# SCH_555-Circuit_2025-10-18.net
KiCad netlist of a schematic drawn in EasyEDA
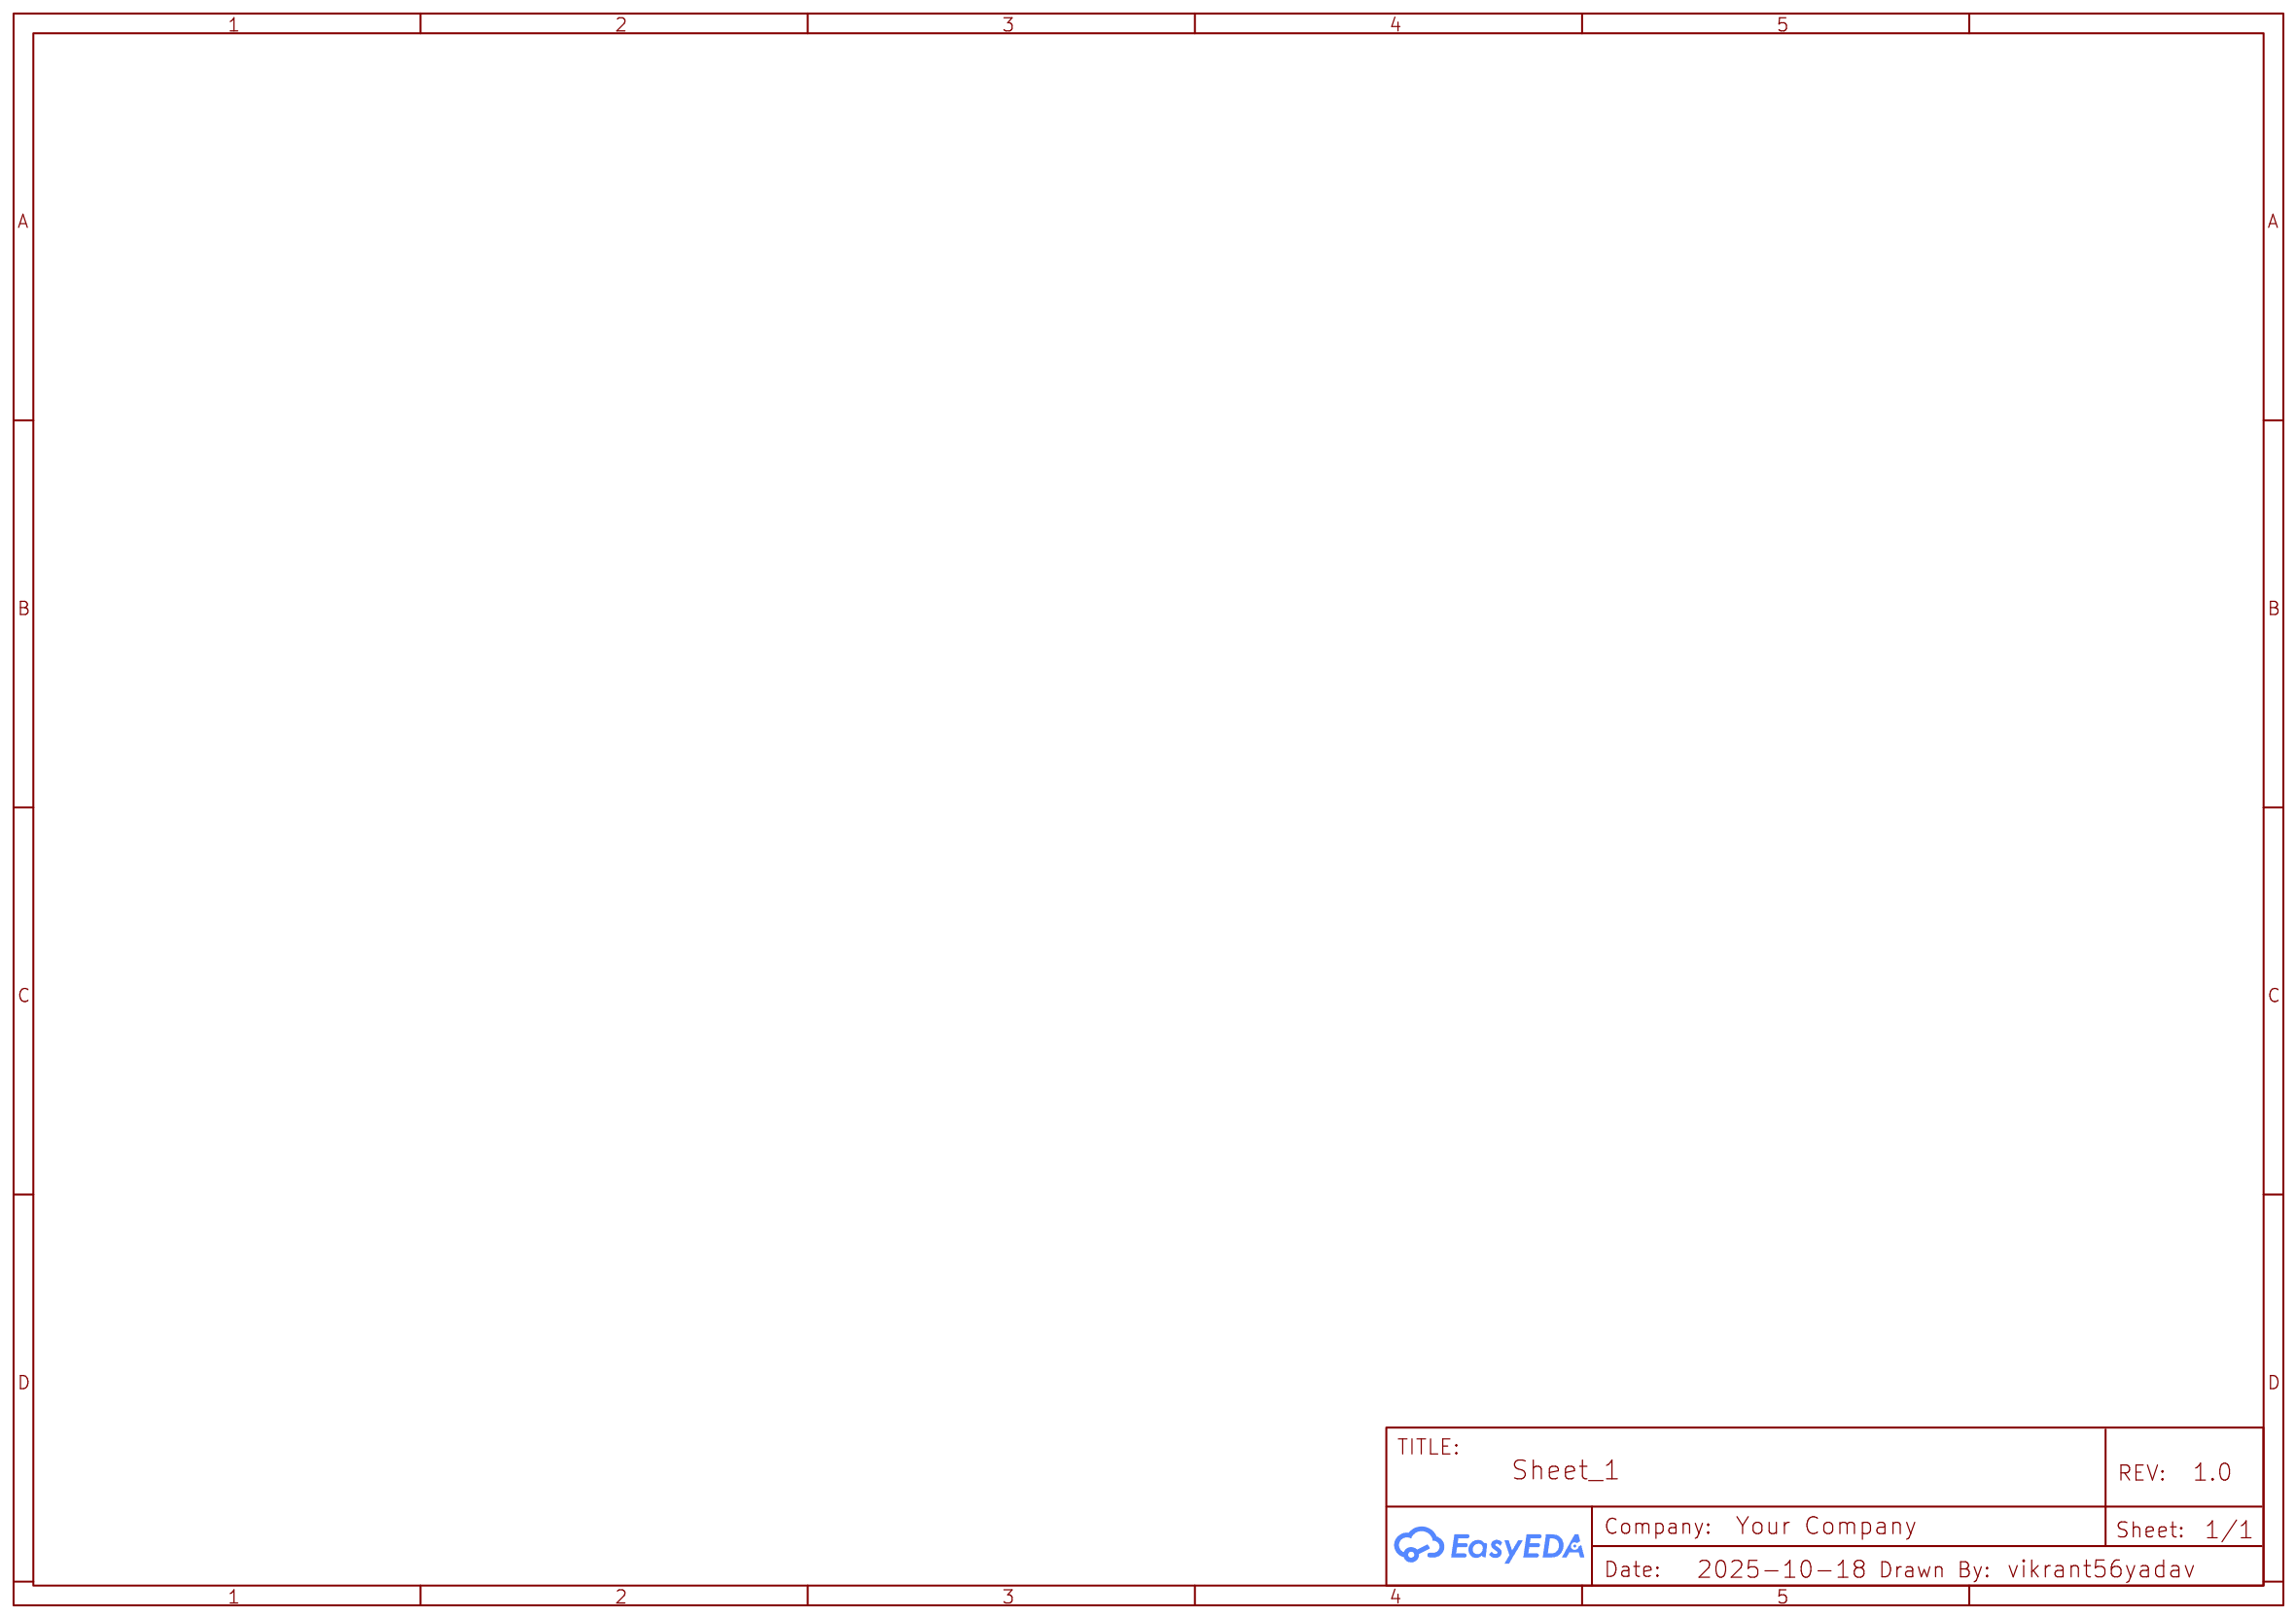
[diagram p0: Sheet_1]
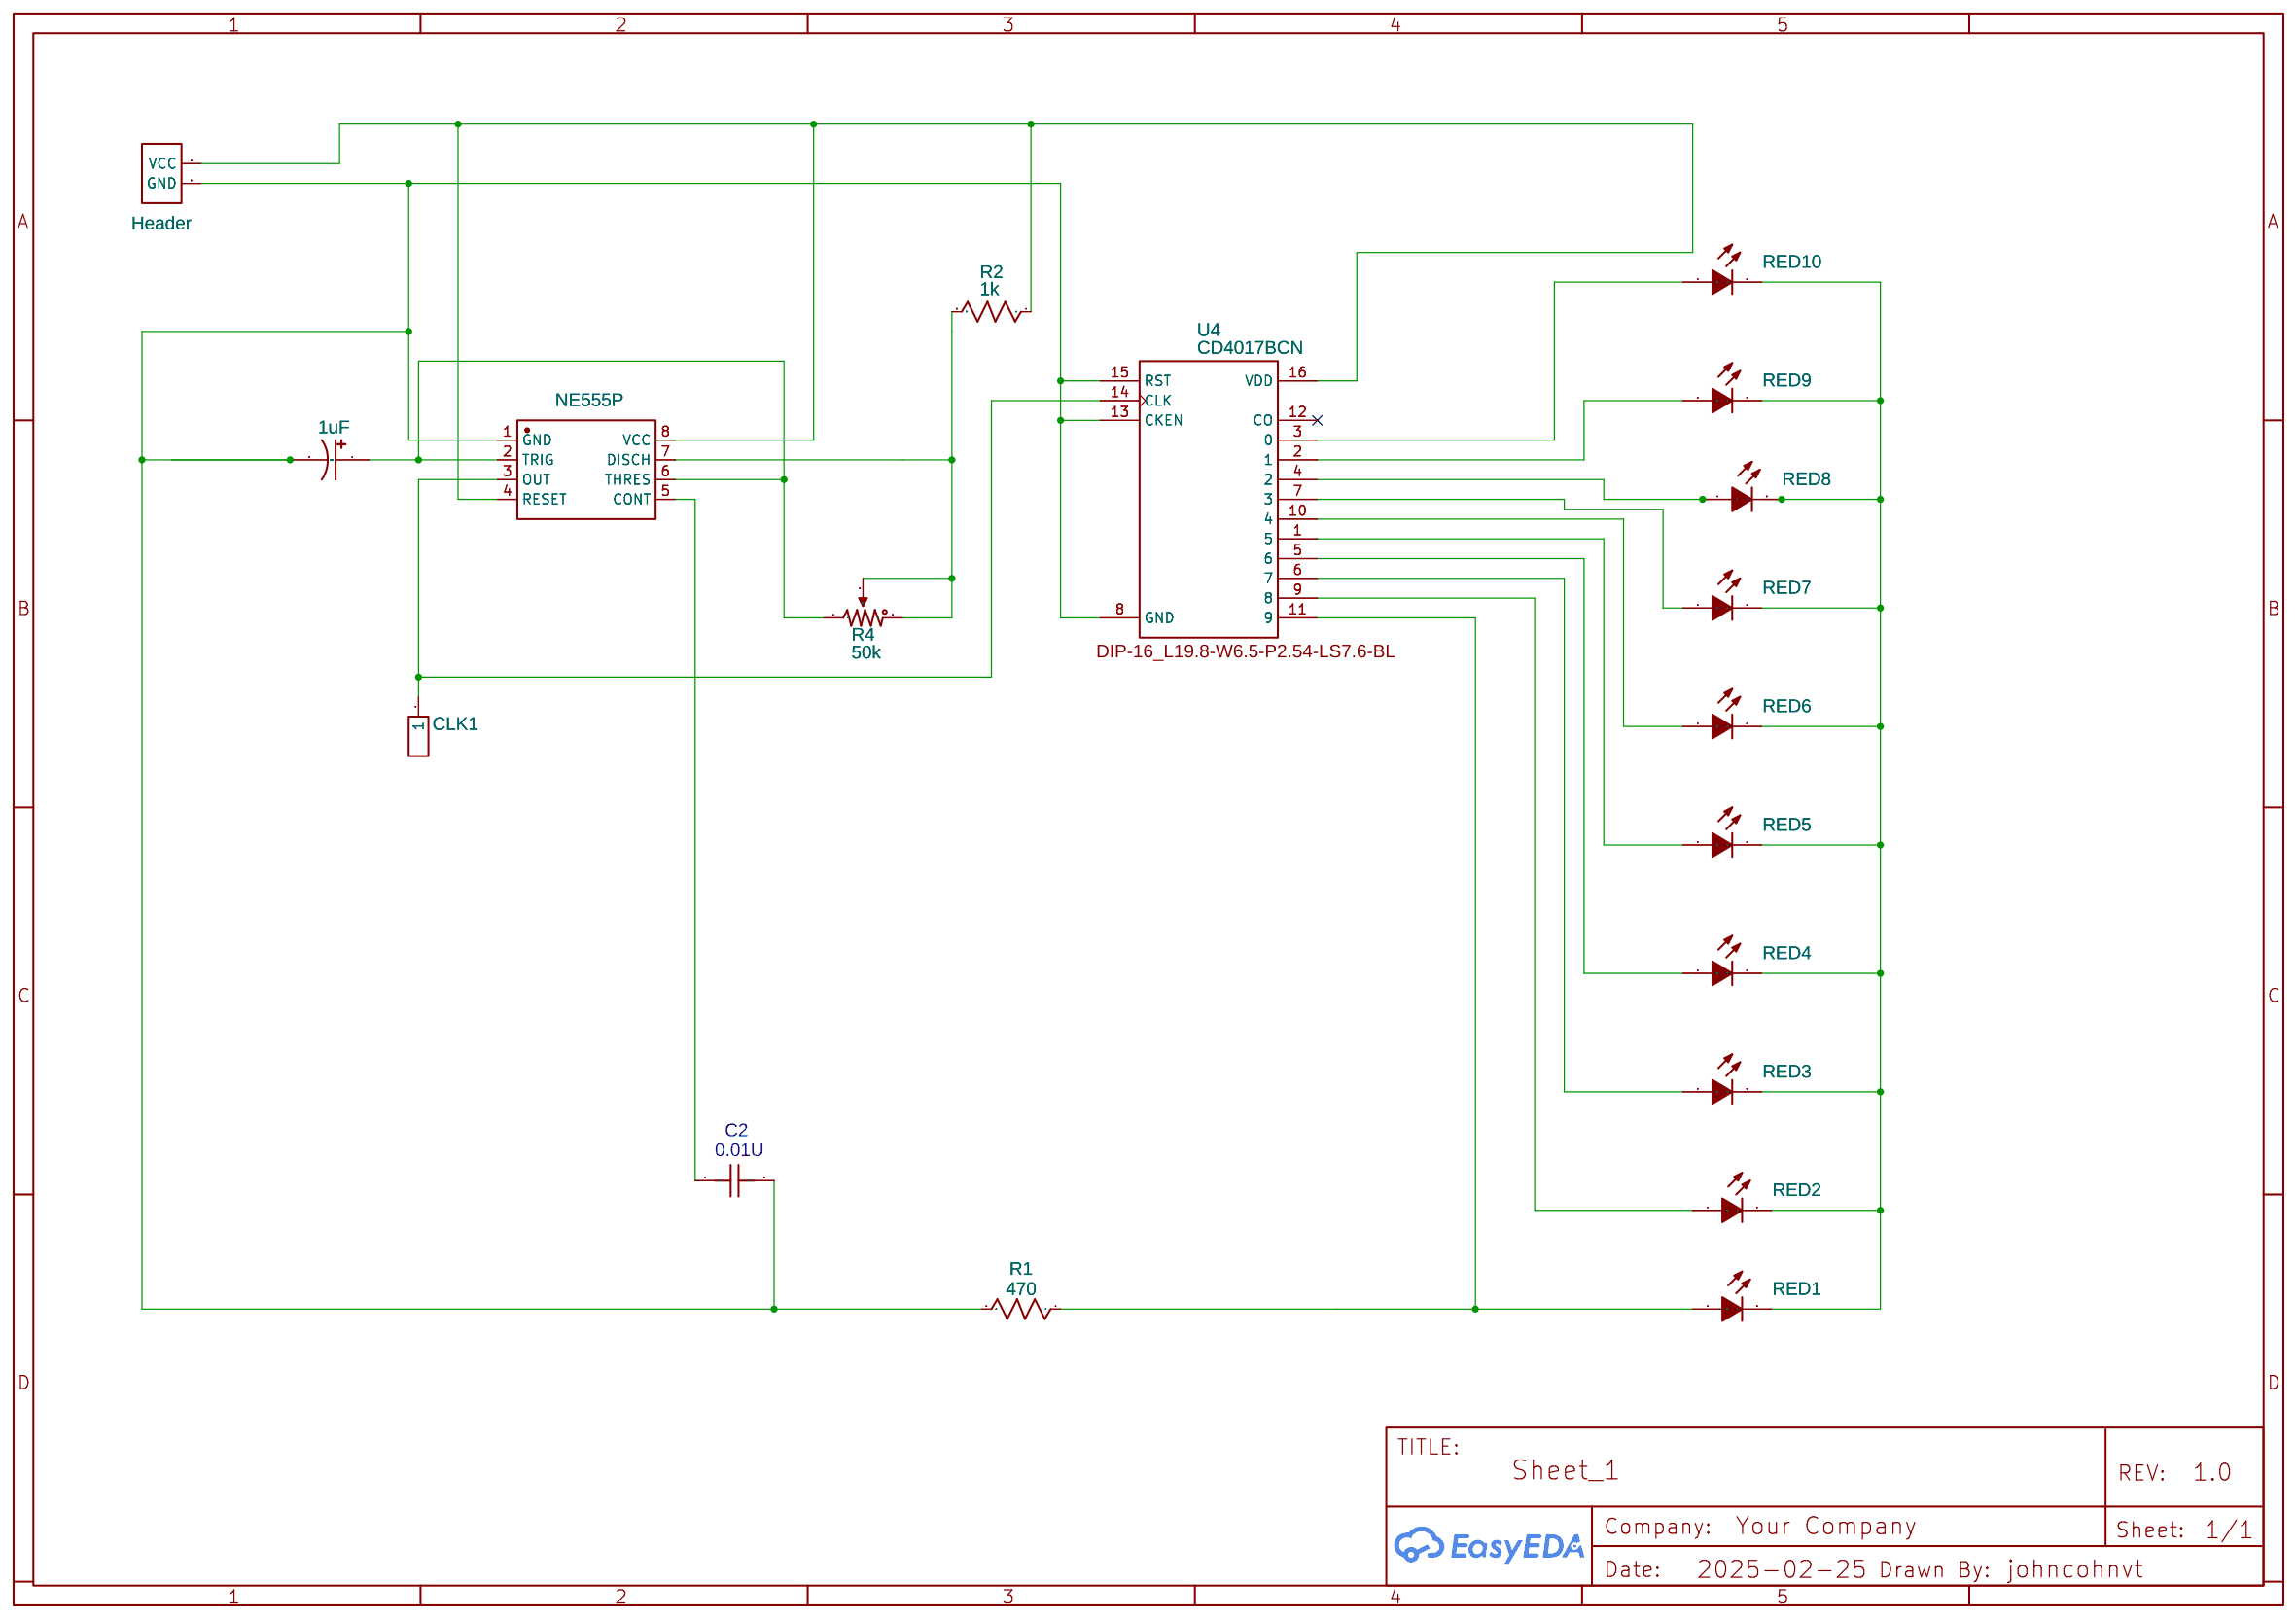
[diagram p1: LED Lab Components copy]

(export (version "E")
  (design (tool "Eeschema 10.0.6"))
  (components
    (comp (ref "C1")
      (value "1uF")
      (fields (field (name "Manufacturer Part") "UVZ1H010MDD") (field (name "Manufacturer") "Nichicon(尼吉康)"))
      (libsource (lib "") (part "UVZ1H010MDD"))
    )
    (comp (ref "C2") (value "0.01u") (libsource (lib "") (part "C_0603_US")))
    (comp (ref "CLK1")
      (value "C81276")
      (fields
        (field (name "Manufacturer Part") "2.54-1*1P针")
        (field (name "Manufacturer") "BOOMELE(Boom Precision Elec)")
      )
      (libsource (lib "") (part "Header-Male-2.54_1x1"))
    )
    (comp (ref "H1") (value "Header") (libsource (lib "") (part "HEADER-FEMALE-2.54_1X2")))
    (comp (ref "R1")
      (value "470")
      (fields (field (name "Manufacturer Part") "?"))
      (libsource (lib "") (part "Resistor"))
    )
    (comp (ref "R2")
      (value "1k")
      (fields (field (name "Manufacturer Part") "?"))
      (libsource (lib "") (part "Resistor"))
    )
    (comp (ref "R4")
      (value "50k")
      (fields (field (name "Manufacturer Part") "?"))
      (libsource (lib "") (part "Potentiometer"))
    )
    (comp (ref "RED1") (value "LED_5MM") (libsource (lib "") (part "LED_5MM")))
    (comp (ref "RED2") (value "LED_5MM") (libsource (lib "") (part "LED_5MM")))
    (comp (ref "RED3") (value "LED_5MM") (libsource (lib "") (part "LED_5MM")))
    (comp (ref "RED4") (value "LED_5MM") (libsource (lib "") (part "LED_5MM")))
    (comp (ref "RED5") (value "LED_5MM") (libsource (lib "") (part "LED_5MM")))
    (comp (ref "RED6") (value "LED_5MM") (libsource (lib "") (part "LED_5MM")))
    (comp (ref "RED7") (value "LED_5MM") (libsource (lib "") (part "LED_5MM")))
    (comp (ref "RED8") (value "LED_5MM") (libsource (lib "") (part "LED_5MM")))
    (comp (ref "RED9") (value "LED_5MM") (libsource (lib "") (part "LED_5MM")))
    (comp (ref "RED10") (value "LED_5MM") (libsource (lib "") (part "LED_5MM")))
    (comp (ref "U2")
      (value "NE555P")
      (fields (field (name "Manufacturer") "TI(德州仪器)"))
      (libsource (lib "") (part "NE555P"))
    )
    (comp (ref "U4") (value "CD4017BCN") (libsource (lib "") (part "CD4017BCN")))
  )
  (nets
    (net (code "1") (name "Net-(H1-GND)") (class "Default")
      (node (ref "C1") (pin "2") (pinfunction "2_2") (pintype "unspecified"))
      (node (ref "C2") (pin "2") (pinfunction "2_2") (pintype "unspecified"))
      (node (ref "H1") (pin "2") (pinfunction "GND_2") (pintype "unspecified"))
      (node (ref "R1") (pin "2") (pinfunction "2_2") (pintype "unspecified"))
      (node (ref "U2") (pin "1") (pinfunction "GND_1") (pintype "unspecified"))
      (node (ref "U4") (pin "13") (pinfunction "CKEN_13") (pintype "unspecified"))
      (node (ref "U4") (pin "15") (pinfunction "RST_15") (pintype "unspecified"))
      (node (ref "U4") (pin "8") (pinfunction "GND_8") (pintype "passive"))
    )
    (net (code "2") (name "Net-(H1-VCC)") (class "Default")
      (node (ref "H1") (pin "1") (pinfunction "VCC_1") (pintype "unspecified"))
      (node (ref "R2") (pin "1") (pinfunction "1_1") (pintype "unspecified"))
      (node (ref "U2") (pin "4") (pinfunction "RESET_4") (pintype "unspecified"))
      (node (ref "U2") (pin "8") (pinfunction "VCC_8") (pintype "unspecified"))
      (node (ref "U4") (pin "16") (pinfunction "VDD_16") (pintype "passive"))
    )
    (net (code "3") (name "Net-(R4-2)") (class "Default")
      (node (ref "R2") (pin "2") (pinfunction "2_2") (pintype "unspecified"))
      (node (ref "R4") (pin "2") (pinfunction "3_2") (pintype "unspecified"))
      (node (ref "R4") (pin "3") (pinfunction "2_3") (pintype "unspecified"))
      (node (ref "U2") (pin "7") (pinfunction "DISCH_7") (pintype "unspecified"))
    )
    (net (code "4") (name "Net-(RED1-A)") (class "Default")
      (node (ref "R1") (pin "1") (pinfunction "1_1") (pintype "unspecified"))
      (node (ref "RED1") (pin "1") (pinfunction "A_1") (pintype "input"))
      (node (ref "U4") (pin "11") (pinfunction "9_11") (pintype "output"))
    )
    (net (code "5") (name "Net-(RED1-K)") (class "Default")
      (node (ref "RED1") (pin "2") (pinfunction "K_2") (pintype "input"))
      (node (ref "RED10") (pin "2") (pinfunction "K_2") (pintype "input"))
      (node (ref "RED2") (pin "2") (pinfunction "K_2") (pintype "input"))
      (node (ref "RED3") (pin "2") (pinfunction "K_2") (pintype "input"))
      (node (ref "RED4") (pin "2") (pinfunction "K_2") (pintype "input"))
      (node (ref "RED5") (pin "2") (pinfunction "K_2") (pintype "input"))
      (node (ref "RED6") (pin "2") (pinfunction "K_2") (pintype "input"))
      (node (ref "RED7") (pin "2") (pinfunction "K_2") (pintype "input"))
      (node (ref "RED8") (pin "2") (pinfunction "K_2") (pintype "input"))
      (node (ref "RED9") (pin "2") (pinfunction "K_2") (pintype "input"))
    )
    (net (code "6") (name "Net-(RED2-A)") (class "Default")
      (node (ref "RED2") (pin "1") (pinfunction "A_1") (pintype "input"))
      (node (ref "U4") (pin "9") (pinfunction "8_9") (pintype "output"))
    )
    (net (code "7") (name "Net-(RED3-A)") (class "Default")
      (node (ref "RED3") (pin "1") (pinfunction "A_1") (pintype "input"))
      (node (ref "U4") (pin "6") (pinfunction "7_6") (pintype "output"))
    )
    (net (code "8") (name "Net-(RED4-A)") (class "Default")
      (node (ref "RED4") (pin "1") (pinfunction "A_1") (pintype "input"))
      (node (ref "U4") (pin "5") (pinfunction "6_5") (pintype "output"))
    )
    (net (code "9") (name "Net-(RED5-A)") (class "Default")
      (node (ref "RED5") (pin "1") (pinfunction "A_1") (pintype "input"))
      (node (ref "U4") (pin "1") (pinfunction "5_1") (pintype "output"))
    )
    (net (code "10") (name "Net-(RED6-A)") (class "Default")
      (node (ref "RED6") (pin "1") (pinfunction "A_1") (pintype "input"))
      (node (ref "U4") (pin "10") (pinfunction "4_10") (pintype "output"))
    )
    (net (code "11") (name "Net-(RED7-A)") (class "Default")
      (node (ref "RED7") (pin "1") (pinfunction "A_1") (pintype "input"))
      (node (ref "U4") (pin "7") (pinfunction "3_7") (pintype "output"))
    )
    (net (code "12") (name "Net-(RED8-A)") (class "Default")
      (node (ref "RED8") (pin "1") (pinfunction "A_1") (pintype "input"))
      (node (ref "U4") (pin "4") (pinfunction "2_4") (pintype "output"))
    )
    (net (code "13") (name "Net-(RED9-A)") (class "Default")
      (node (ref "RED9") (pin "1") (pinfunction "A_1") (pintype "input"))
      (node (ref "U4") (pin "2") (pinfunction "1_2") (pintype "output"))
    )
    (net (code "14") (name "Net-(RED10-A)") (class "Default")
      (node (ref "RED10") (pin "1") (pinfunction "A_1") (pintype "input"))
      (node (ref "U4") (pin "3") (pinfunction "0_3") (pintype "output"))
    )
    (net (code "15") (name "Net-(U2-CONT)") (class "Default")
      (node (ref "C2") (pin "1") (pinfunction "1_1") (pintype "unspecified"))
      (node (ref "U2") (pin "5") (pinfunction "CONT_5") (pintype "unspecified"))
    )
    (net (code "16") (name "Net-(U2-OUT)") (class "Default")
      (node (ref "CLK1") (pin "1") (pinfunction "1_1") (pintype "unspecified"))
      (node (ref "U2") (pin "3") (pinfunction "OUT_3") (pintype "unspecified"))
      (node (ref "U4") (pin "14") (pinfunction "CLK_14") (pintype "unspecified"))
    )
    (net (code "17") (name "Net-(U2-THRES)") (class "Default")
      (node (ref "C1") (pin "1") (pinfunction "1_1") (pintype "unspecified"))
      (node (ref "R4") (pin "1") (pinfunction "1_1") (pintype "unspecified"))
      (node (ref "U2") (pin "2") (pinfunction "TRIG_2") (pintype "unspecified"))
      (node (ref "U2") (pin "6") (pinfunction "THRES_6") (pintype "unspecified"))
    )
    (net (code "18") (name "unconnected-(U4-CO-Pad12)") (class "Default")
      (node (ref "U4") (pin "12") (pinfunction "CO_12") (pintype "output+no_connect"))
    )
  )
)
